# 4_IMU.net
KiCad netlist of a schematic drawn in Altium Designer
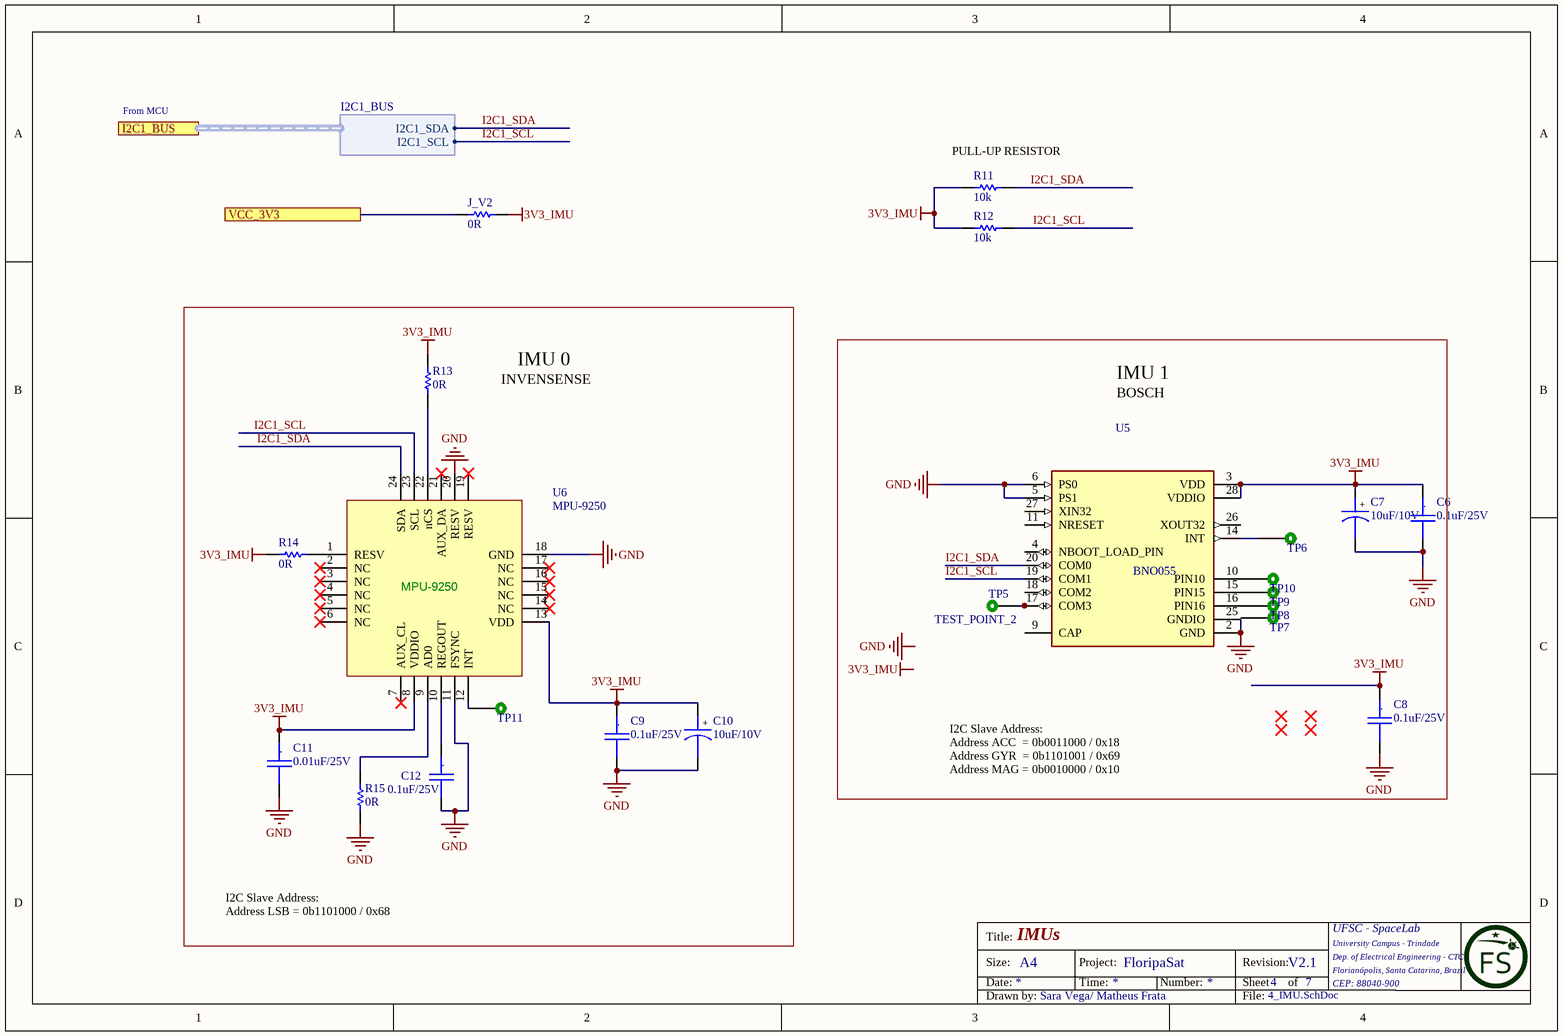
[diagram p0: 4_IMU.SchDoc]

(export (version "E")
  (design (tool "Eeschema 10.0.6"))
  (components
    (comp (ref "C6")
      (value "0.1uF/25V")
      (footprint "CC0805")
      (description "CAP CER 0.1UF 25V 10% X7R 0805")
      (fields (field (name "PARTNUMBER") "CC0805KRX7R8BB104"))
      (libsource (lib "FloripaSatSchlib") (part "Cap_Cer_X7R_0.1uF_25V_0805"))
    )
    (comp (ref "C7")
      (value "10uF/10V")
      (footprint "FloripaSatPcbLib:CC0805_Tantalum")
      (description "CAP Tantalum 10uF 10V 20% 0805")
      (fields (field (name "PARTNUMBER") "TPSP106M010R2000"))
      (libsource (lib "FloripaSatSchlib") (part "Cap_Tant_SMD_10uF_10V_0805"))
    )
    (comp (ref "C8")
      (value "0.1uF/25V")
      (footprint "CC0805")
      (description "CAP CER 0.1UF 25V 10% X7R 0805")
      (fields (field (name "PARTNUMBER") "CC0805KRX7R8BB104"))
      (libsource (lib "FloripaSatSchlib") (part "Cap_Cer_X7R_0.1uF_25V_0805"))
    )
    (comp (ref "C9")
      (value "0.1uF/25V")
      (footprint "CC0805")
      (description "CAP CER 0.1UF 25V 10% X7R 0805")
      (fields (field (name "PARTNUMBER") "CC0805KRX7R8BB104"))
      (libsource (lib "FloripaSatSchlib") (part "Cap_Cer_X7R_0.1uF_25V_0805"))
    )
    (comp (ref "C10")
      (value "10uF/10V")
      (footprint "FloripaSatPcbLib:CC0805_Tantalum")
      (description "CAP Tantalum 10uF 10V 20% 0805")
      (fields (field (name "PARTNUMBER") "TPSP106M010R2000"))
      (libsource (lib "FloripaSatSchlib") (part "Cap_Tant_SMD_10uF_10V_0805"))
    )
    (comp (ref "C11")
      (value "0.01uF/25V")
      (footprint "CC0805")
      (description "CAP CER 0.01uF 25V 10% X7R 0805")
      (fields (field (name "PARTNUMBER") "CL21B103KAANNNC"))
      (libsource (lib "FloripaSatSchlib") (part "Cap_Cer_X7R_0.01uF_50V_0805"))
    )
    (comp (ref "C12")
      (value "0.1uF/25V")
      (footprint "CC0805")
      (description "CAP CER 0.1UF 25V 10% X7R 0805")
      (fields (field (name "PARTNUMBER") "CC0805KRX7R8BB104"))
      (libsource (lib "FloripaSatSchlib") (part "Cap_Cer_X7R_0.1uF_25V_0805"))
    )
    (comp (ref "J_V2")
      (value "0R")
      (footprint "FloripaSatPcbLib:0805")
      (description "RES 0R OHM 1/16W JUMPER 0805")
      (fields (field (name "PARTNUMBER") "CRCW08050000Z0EA"))
      (libsource (lib "FloripaSatSchlib") (part "R0R_JUMPER_1/16W_0805"))
    )
    (comp (ref "R11")
      (value "10k")
      (footprint "0805")
      (description "RES 10K OHM 1/8W 1%  0805")
      (fields (field (name "PARTNUMBER") "CRCW080510K0FKEA"))
      (libsource (lib "FloripaSatSchlib") (part "R10k_1%_1/8W_0805"))
    )
    (comp (ref "R12")
      (value "10k")
      (footprint "0805")
      (description "RES 10K OHM 1/8W 1%  0805")
      (fields (field (name "PARTNUMBER") "CRCW080510K0FKEA"))
      (libsource (lib "FloripaSatSchlib") (part "R10k_1%_1/8W_0805"))
    )
    (comp (ref "R13")
      (value "0R")
      (footprint "FloripaSatPcbLib:0805")
      (description "RES 0R OHM 1/16W JUMPER 0805")
      (fields (field (name "PARTNUMBER") "CRCW08050000Z0EA"))
      (libsource (lib "FloripaSatSchlib") (part "R0R_JUMPER_1/16W_0805"))
    )
    (comp (ref "R14")
      (value "0R")
      (footprint "FloripaSatPcbLib:0805")
      (description "RES 0R OHM 1/16W JUMPER 0805")
      (fields (field (name "PARTNUMBER") "CRCW08050000Z0EA"))
      (libsource (lib "FloripaSatSchlib") (part "R0R_JUMPER_1/16W_0805"))
    )
    (comp (ref "R15")
      (value "0R")
      (footprint "FloripaSatPcbLib:0805")
      (description "RES 0R OHM 1/16W JUMPER 0805")
      (fields (field (name "PARTNUMBER") "CRCW08050000Z0EA"))
      (libsource (lib "FloripaSatSchlib") (part "R0R_JUMPER_1/16W_0805"))
    )
    (comp (ref "TP5")
      (value "TEST_POINT_2")
      (footprint "TEST_POINT_2")
      (description "Test point")
      (libsource (lib "FloripaSatSchlib") (part "TEST_POINT_2"))
    )
    (comp (ref "TP6")
      (value "TEST_POINT_2")
      (footprint "TEST_POINT_2")
      (description "Test point")
      (libsource (lib "FloripaSatSchlib") (part "TEST_POINT_2"))
    )
    (comp (ref "TP7")
      (value "TEST_POINT_2")
      (footprint "TEST_POINT_2")
      (description "Test point")
      (libsource (lib "FloripaSatSchlib") (part "TEST_POINT_2"))
    )
    (comp (ref "TP8")
      (value "TEST_POINT_2")
      (footprint "TEST_POINT_2")
      (description "Test point")
      (libsource (lib "FloripaSatSchlib") (part "TEST_POINT_2"))
    )
    (comp (ref "TP9")
      (value "TEST_POINT_2")
      (footprint "TEST_POINT_2")
      (description "Test point")
      (libsource (lib "FloripaSatSchlib") (part "TEST_POINT_2"))
    )
    (comp (ref "TP10")
      (value "TEST_POINT_2")
      (footprint "TEST_POINT_2")
      (description "Test point")
      (libsource (lib "FloripaSatSchlib") (part "TEST_POINT_2"))
    )
    (comp (ref "TP11")
      (value "TEST_POINT_2")
      (footprint "TEST_POINT_2")
      (description "Test point")
      (libsource (lib "FloripaSatSchlib") (part "TEST_POINT_2"))
    )
    (comp (ref "U5")
      (value "BNO055")
      (footprint "LGA28R50P4X10_380X520X100")
      (description "BNO055 9-axis Absolute Orientation Sensor ( SiP ) w/Sensors and Sensor Fusion")
      (libsource (lib "BNO055") (part "BNO055"))
    )
    (comp (ref "U6")
      (value "MPU-9250")
      (footprint "QFN24P300X300X105-25N")
      (description "SMD Gyroscope/Accelerometer/Magnetometer Sensor; 9-AXIS")
      (libsource (lib "FloripaSatSchlib") (part "MPU9250"))
    )
  )
  (nets
    (net (code "2") (name "/I2C1_SCL") (class "Default")
      (node (ref "R12") (pin "1") (pinfunction "1_1") (pintype "passive"))
      (node (ref "U5") (pin "19") (pinfunction "COM1_19") (pintype "bidirectional"))
      (node (ref "U6") (pin "23") (pinfunction "SCL_23") (pintype "passive"))
    )
    (net (code "3") (name "/I2C1_SDA") (class "Default")
      (node (ref "R11") (pin "1") (pinfunction "1_1") (pintype "passive"))
      (node (ref "U5") (pin "20") (pinfunction "COM0_20") (pintype "bidirectional"))
      (node (ref "U6") (pin "24") (pinfunction "SDA_24") (pintype "passive"))
    )
    (net (code "4") (name "/VCC_3V3") (class "Default")
      (node (ref "J_V2") (pin "2") (pinfunction "2_2") (pintype "passive"))
    )
    (net (code "6") (name "3V3_IMU") (class "Default")
      (node (ref "C10") (pin "1") (pinfunction "1_1") (pintype "passive"))
      (node (ref "C11") (pin "1") (pinfunction "1_1") (pintype "passive"))
      (node (ref "C6") (pin "1") (pinfunction "1_1") (pintype "passive"))
      (node (ref "C7") (pin "1") (pinfunction "1_1") (pintype "passive"))
      (node (ref "C8") (pin "1") (pinfunction "1_1") (pintype "passive"))
      (node (ref "C9") (pin "1") (pinfunction "1_1") (pintype "passive"))
      (node (ref "J_V2") (pin "1") (pinfunction "1_1") (pintype "passive"))
      (node (ref "R11") (pin "2") (pinfunction "2_2") (pintype "passive"))
      (node (ref "R12") (pin "2") (pinfunction "2_2") (pintype "passive"))
      (node (ref "R13") (pin "2") (pinfunction "2_2") (pintype "passive"))
      (node (ref "R14") (pin "2") (pinfunction "2_2") (pintype "passive"))
      (node (ref "U5") (pin "28") (pinfunction "VDDIO_28") (pintype "power_in"))
      (node (ref "U5") (pin "3") (pinfunction "VDD_3") (pintype "power_in"))
      (node (ref "U6") (pin "13") (pinfunction "VDD_13") (pintype "passive"))
      (node (ref "U6") (pin "8") (pinfunction "VDDIO_8") (pintype "passive"))
    )
    (net (code "7") (name "GND") (class "Default")
      (node (ref "C10") (pin "2") (pinfunction "2_2") (pintype "passive"))
      (node (ref "C11") (pin "2") (pinfunction "2_2") (pintype "passive"))
      (node (ref "C12") (pin "2") (pinfunction "2_2") (pintype "passive"))
      (node (ref "C6") (pin "2") (pinfunction "2_2") (pintype "passive"))
      (node (ref "C7") (pin "2") (pinfunction "2_2") (pintype "passive"))
      (node (ref "C8") (pin "2") (pinfunction "2_2") (pintype "passive"))
      (node (ref "C9") (pin "2") (pinfunction "2_2") (pintype "passive"))
      (node (ref "R15") (pin "2") (pinfunction "2_2") (pintype "passive"))
      (node (ref "U5") (pin "2") (pinfunction "GND_2") (pintype "power_in"))
      (node (ref "U5") (pin "25") (pinfunction "GNDIO_25") (pintype "power_in"))
      (node (ref "U5") (pin "5") (pinfunction "PS1_5") (pintype "input"))
      (node (ref "U5") (pin "6") (pinfunction "PS0_6") (pintype "input"))
      (node (ref "U6") (pin "11") (pinfunction "FSYNC_11") (pintype "passive"))
      (node (ref "U6") (pin "18") (pinfunction "GND_18") (pintype "passive"))
      (node (ref "U6") (pin "20") (pinfunction "RESV_20") (pintype "passive"))
    )
    (net (code "8") (name "Net-(R14-Pad1)") (class "Default")
      (node (ref "R14") (pin "1") (pinfunction "1_1") (pintype "passive"))
      (node (ref "U6") (pin "1") (pinfunction "RESV_1") (pintype "passive"))
    )
    (net (code "9") (name "Net-(U5-COM3)") (class "Default")
      (node (ref "TP5") (pin "1") (pinfunction "1_1") (pintype "passive"))
      (node (ref "U5") (pin "17") (pinfunction "COM3_17") (pintype "bidirectional"))
    )
    (net (code "10") (name "Net-(U5-INT)") (class "Default")
      (node (ref "TP6") (pin "1") (pinfunction "1_1") (pintype "passive"))
      (node (ref "U5") (pin "14") (pinfunction "INT_14") (pintype "output"))
    )
    (net (code "11") (name "Net-(U5-PIN10)") (class "Default")
      (node (ref "TP10") (pin "1") (pinfunction "1_1") (pintype "passive"))
      (node (ref "U5") (pin "10") (pinfunction "PIN10_10") (pintype "power_in"))
    )
    (net (code "12") (name "Net-(U5-PIN15)") (class "Default")
      (node (ref "TP9") (pin "1") (pinfunction "1_1") (pintype "passive"))
      (node (ref "U5") (pin "15") (pinfunction "PIN15_15") (pintype "power_in"))
    )
    (net (code "13") (name "Net-(U5-PIN16)") (class "Default")
      (node (ref "TP8") (pin "1") (pinfunction "1_1") (pintype "passive"))
      (node (ref "U5") (pin "16") (pinfunction "PIN16_16") (pintype "power_in"))
    )
    (net (code "14") (name "Net-(U6-AD0)") (class "Default")
      (node (ref "R15") (pin "1") (pinfunction "1_1") (pintype "passive"))
      (node (ref "U6") (pin "9") (pinfunction "AD0_9") (pintype "passive"))
    )
    (net (code "15") (name "Net-(U6-INT)") (class "Default")
      (node (ref "TP11") (pin "1") (pinfunction "1_1") (pintype "passive"))
      (node (ref "U6") (pin "12") (pinfunction "INT_12") (pintype "passive"))
    )
    (net (code "16") (name "Net-(U6-REGOUT)") (class "Default")
      (node (ref "C12") (pin "1") (pinfunction "1_1") (pintype "passive"))
      (node (ref "U6") (pin "10") (pinfunction "REGOUT_10") (pintype "passive"))
    )
    (net (code "17") (name "Net-(U6-nCS)") (class "Default")
      (node (ref "R13") (pin "1") (pinfunction "1_1") (pintype "passive"))
      (node (ref "U6") (pin "22") (pinfunction "nCS_22") (pintype "passive"))
    )
    (net (code "18") (name "unconnected-(TP7-Pad1)") (class "Default")
      (node (ref "TP7") (pin "1") (pinfunction "1_1") (pintype "passive"))
    )
    (net (code "19") (name "unconnected-(U5-CAP-Pad9)") (class "Default")
      (node (ref "U5") (pin "9") (pinfunction "CAP_9") (pintype "passive"))
    )
    (net (code "20") (name "unconnected-(U5-COM2-Pad18)") (class "Default")
      (node (ref "U5") (pin "18") (pinfunction "COM2_18") (pintype "bidirectional"))
    )
    (net (code "21") (name "unconnected-(U5-NBOOT_LOAD_PIN-Pad4)") (class "Default")
      (node (ref "U5") (pin "4") (pinfunction "NBOOT_LOAD_PIN_4") (pintype "bidirectional"))
    )
    (net (code "22") (name "unconnected-(U5-NRESET-Pad11)") (class "Default")
      (node (ref "U5") (pin "11") (pinfunction "NRESET_11") (pintype "input"))
    )
    (net (code "23") (name "unconnected-(U5-XIN32-Pad27)") (class "Default")
      (node (ref "U5") (pin "27") (pinfunction "XIN32_27") (pintype "input"))
    )
    (net (code "24") (name "unconnected-(U5-XOUT32-Pad26)") (class "Default")
      (node (ref "U5") (pin "26") (pinfunction "XOUT32_26") (pintype "output"))
    )
    (net (code "25") (name "unconnected-(U6-AUX_CL-Pad7)") (class "Default")
      (node (ref "U6") (pin "7") (pinfunction "AUX_CL_7") (pintype "passive+no_connect"))
    )
    (net (code "26") (name "unconnected-(U6-AUX_DA-Pad21)") (class "Default")
      (node (ref "U6") (pin "21") (pinfunction "AUX_DA_21") (pintype "passive+no_connect"))
    )
    (net (code "27") (name "unconnected-(U6-NC-Pad2)") (class "Default")
      (node (ref "U6") (pin "2") (pinfunction "NC_2") (pintype "passive+no_connect"))
    )
    (net (code "28") (name "unconnected-(U6-NC-Pad3)") (class "Default")
      (node (ref "U6") (pin "3") (pinfunction "NC_3") (pintype "passive+no_connect"))
    )
    (net (code "29") (name "unconnected-(U6-NC-Pad4)") (class "Default")
      (node (ref "U6") (pin "4") (pinfunction "NC_4") (pintype "passive+no_connect"))
    )
    (net (code "30") (name "unconnected-(U6-NC-Pad5)") (class "Default")
      (node (ref "U6") (pin "5") (pinfunction "NC_5") (pintype "passive+no_connect"))
    )
    (net (code "31") (name "unconnected-(U6-NC-Pad6)") (class "Default")
      (node (ref "U6") (pin "6") (pinfunction "NC_6") (pintype "passive+no_connect"))
    )
    (net (code "32") (name "unconnected-(U6-NC-Pad14)") (class "Default")
      (node (ref "U6") (pin "14") (pinfunction "NC_14") (pintype "passive+no_connect"))
    )
    (net (code "33") (name "unconnected-(U6-NC-Pad15)") (class "Default")
      (node (ref "U6") (pin "15") (pinfunction "NC_15") (pintype "passive+no_connect"))
    )
    (net (code "34") (name "unconnected-(U6-NC-Pad16)") (class "Default")
      (node (ref "U6") (pin "16") (pinfunction "NC_16") (pintype "passive+no_connect"))
    )
    (net (code "35") (name "unconnected-(U6-NC-Pad17)") (class "Default")
      (node (ref "U6") (pin "17") (pinfunction "NC_17") (pintype "passive+no_connect"))
    )
    (net (code "36") (name "unconnected-(U6-RESV-Pad19)") (class "Default")
      (node (ref "U6") (pin "19") (pinfunction "RESV_19") (pintype "passive+no_connect"))
    )
  )
)
